# PLD_FRAM-Memory.net
KiCad netlist of a schematic drawn in Altium Designer
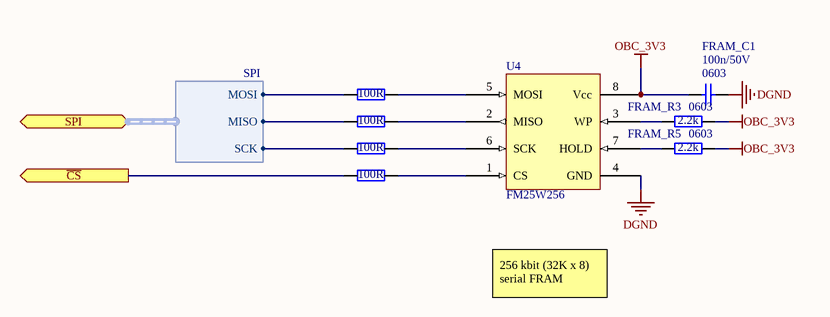
[diagram p0: PLD_FRAM-Memory.SchDoc]

(export (version "E")
  (design (tool "Eeschema 10.0.6"))
  (components
    (comp (ref "FRAM_C1")
      (value "100n/50V")
      (footprint "SMD_Capacitor_0603")
      (description "Ceramic Cap Kemet COTS 100n/50V X7R 0603")
      (fields
        (field (name "MANUFACTURER") "Kemet")
        (field (name "MANUFACTURERPARTNUMBER") "C0603T104K5RALTU")
        (field (name "PACKAGE") "0603")
      )
      (libsource (lib "capacitors") (part "Cer_C0603T104K5RALTU"))
    )
    (comp (ref "FRAM_R1")
      (value "100R")
      (footprint "SMD_RESISTOR_ARRAY_YC124")
      (description "RESISTOR ARRAY, 4 x 0402")
      (libsource (lib "resistors") (part "4ResPack"))
    )
    (comp (ref "FRAM_R3")
      (value "2.2k")
      (footprint "SMD_Resistor_0603")
      (description "2.2k/1% Vishay CRCW 0603 Resistor. 100mW, 100ppm, 75V.")
      (fields
        (field (name "MANUFACTURERPARTNUMBER") "CRCW06032K20FKxxxx")
        (field (name "MANUFACTURER") "Vishay")
        (field (name "PACKAGE") "0603")
      )
      (libsource (lib "resistors") (part "CRCW06032K20FKxxxx"))
    )
    (comp (ref "FRAM_R5")
      (value "2.2k")
      (footprint "SMD_Resistor_0603")
      (description "2.2k/1% Vishay CRCW 0603 Resistor. 100mW, 100ppm, 75V.")
      (fields
        (field (name "MANUFACTURERPARTNUMBER") "CRCW06032K20FKxxxx")
        (field (name "MANUFACTURER") "Vishay")
        (field (name "PACKAGE") "0603")
      )
      (libsource (lib "resistors") (part "CRCW06032K20FKxxxx"))
    )
    (comp (ref "U4")
      (value "FM25W256")
      (footprint "DIP8 ADAPTER")
      (description "256Kb (8k x 32) SPI F-RAM")
      (libsource (lib "microcircuits") (part "FM25W256"))
    )
  )
  (nets
    (net (code "2") (name "/MISO") (class "Default")
      (node (ref "FRAM_R1") (pin "5") (pinfunction "5_5") (pintype "passive"))
    )
    (net (code "3") (name "/MOSI") (class "Default")
      (node (ref "FRAM_R1") (pin "8") (pinfunction "8_8") (pintype "passive"))
    )
    (net (code "4") (name "/SCK") (class "Default")
      (node (ref "FRAM_R1") (pin "7") (pinfunction "7_7") (pintype "passive"))
    )
    (net (code "6") (name "/~{CS}") (class "Default")
      (node (ref "FRAM_R1") (pin "6") (pinfunction "6_6") (pintype "passive"))
    )
    (net (code "7") (name "DGND") (class "Default")
      (node (ref "FRAM_C1") (pin "1") (pinfunction "1_1") (pintype "passive"))
      (node (ref "U4") (pin "4") (pinfunction "GND_4") (pintype "power_in"))
    )
    (net (code "8") (name "Net-(U4-CS)") (class "Default")
      (node (ref "FRAM_R1") (pin "3") (pinfunction "3_3") (pintype "passive"))
      (node (ref "U4") (pin "1") (pinfunction "CS_1") (pintype "input"))
    )
    (net (code "9") (name "Net-(U4-HOLD)") (class "Default")
      (node (ref "FRAM_R5") (pin "1") (pinfunction "1_1") (pintype "passive"))
      (node (ref "U4") (pin "7") (pinfunction "HOLD_7") (pintype "input"))
    )
    (net (code "10") (name "Net-(U4-MISO)") (class "Default")
      (node (ref "FRAM_R1") (pin "4") (pinfunction "4_4") (pintype "passive"))
      (node (ref "U4") (pin "2") (pinfunction "MISO_2") (pintype "output"))
    )
    (net (code "11") (name "Net-(U4-MOSI)") (class "Default")
      (node (ref "FRAM_R1") (pin "1") (pinfunction "1_1") (pintype "passive"))
      (node (ref "U4") (pin "5") (pinfunction "MOSI_5") (pintype "input"))
    )
    (net (code "12") (name "Net-(U4-SCK)") (class "Default")
      (node (ref "FRAM_R1") (pin "2") (pinfunction "2_2") (pintype "passive"))
      (node (ref "U4") (pin "6") (pinfunction "SCK_6") (pintype "input"))
    )
    (net (code "13") (name "Net-(U4-WP)") (class "Default")
      (node (ref "FRAM_R3") (pin "1") (pinfunction "1_1") (pintype "passive"))
      (node (ref "U4") (pin "3") (pinfunction "WP_3") (pintype "input"))
    )
    (net (code "14") (name "OBC_3V3") (class "Default")
      (node (ref "FRAM_C1") (pin "2") (pinfunction "2_2") (pintype "passive"))
      (node (ref "FRAM_R3") (pin "2") (pinfunction "2_2") (pintype "passive"))
      (node (ref "FRAM_R5") (pin "2") (pinfunction "2_2") (pintype "passive"))
      (node (ref "U4") (pin "8") (pinfunction "Vcc_8") (pintype "power_in"))
    )
  )
)
